# USB_Protect_A.net
KiCad netlist of a schematic drawn in EAGLE
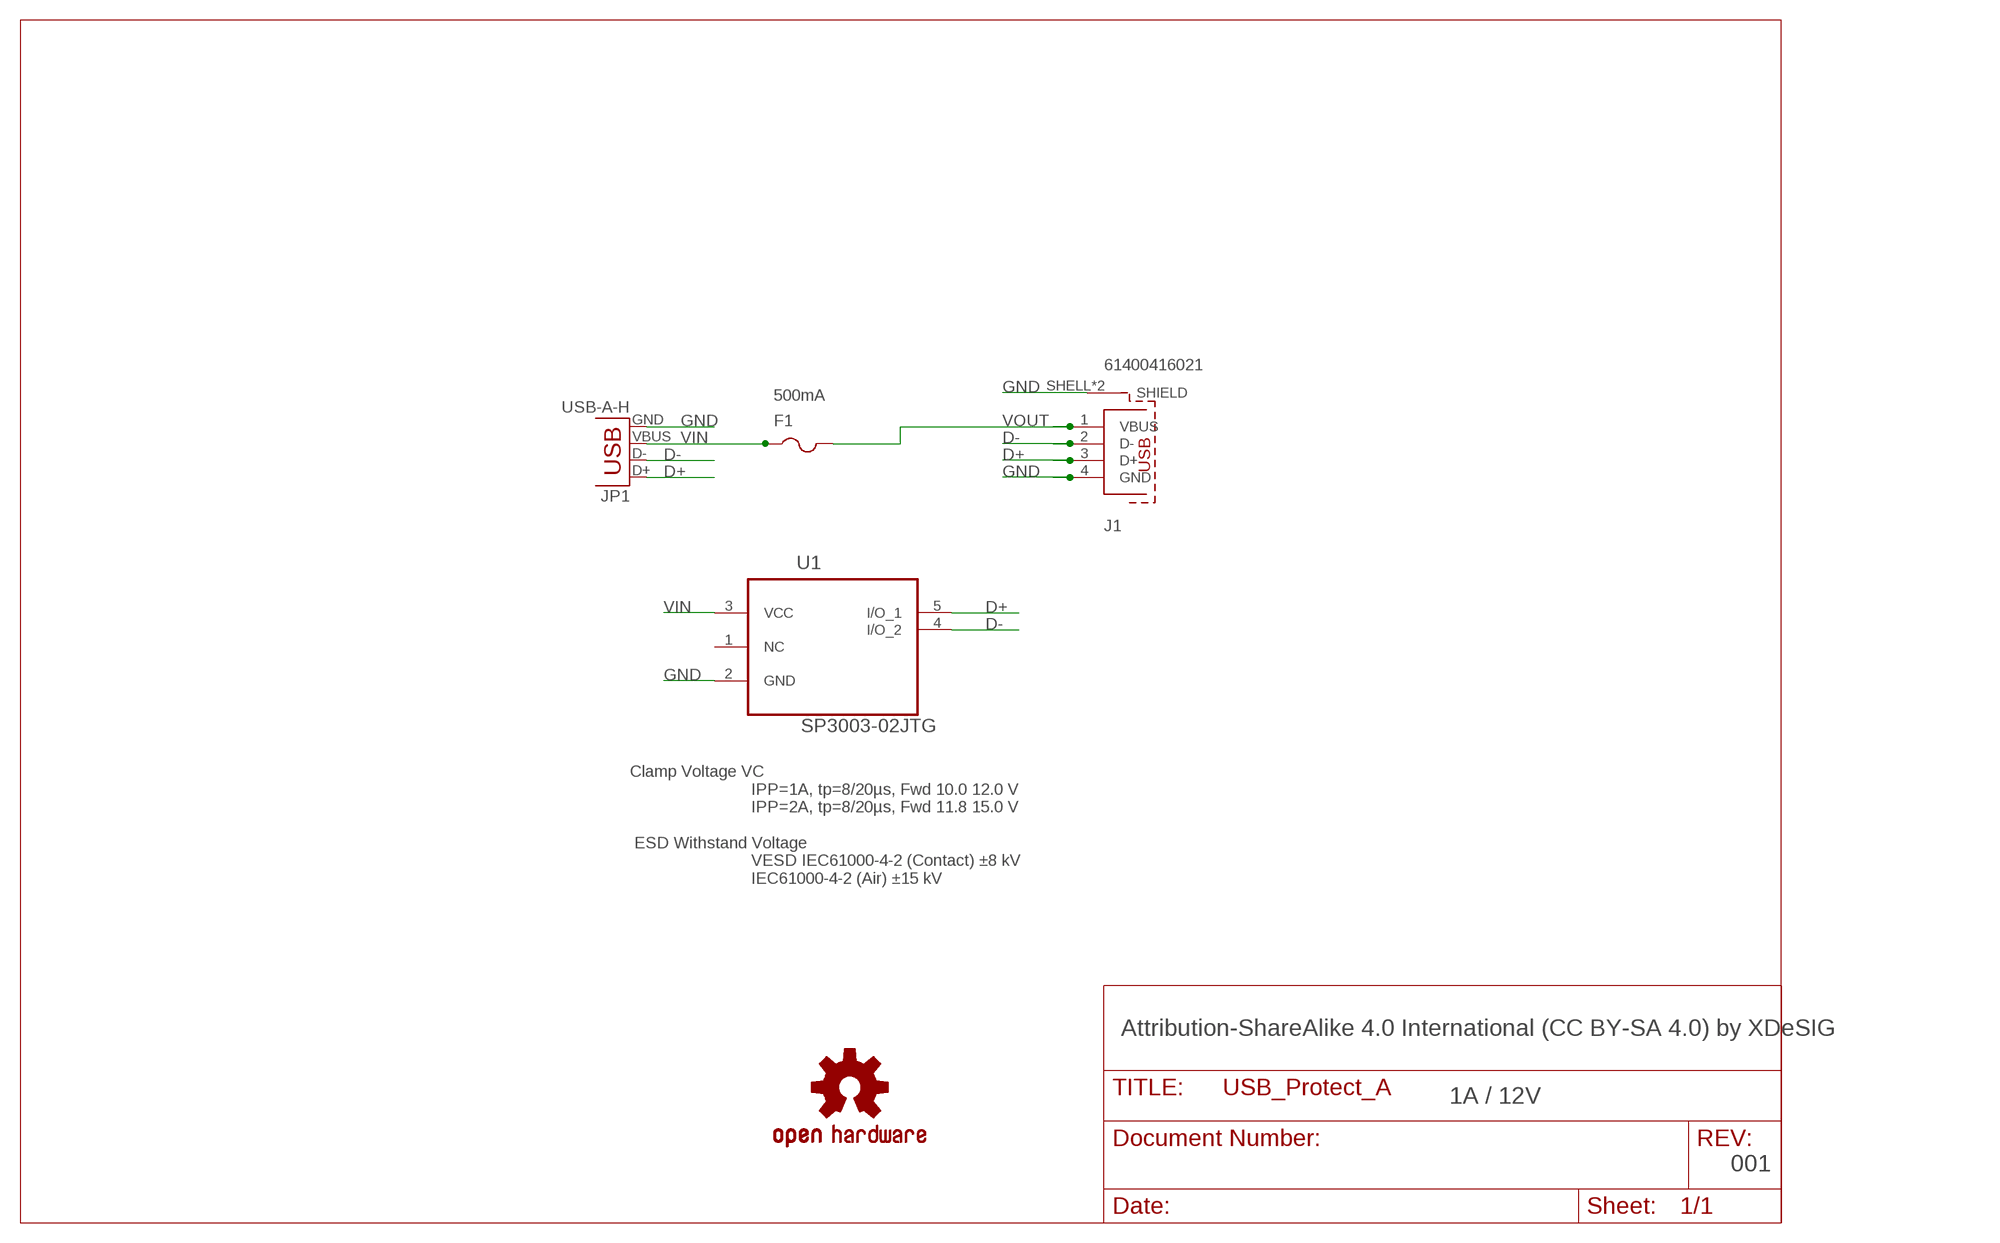
[diagram p0: schematic, sheet 1]

(export (version "E")
  (design (tool "Eeschema 10.0.6"))
  (components
    (comp (ref "F1")
      (value "500mA")
      (footprint "eagle-import:R1206")
      (libsource (lib "eagle-import") (part "PTCFUSE-1206"))
    )
    (comp (ref "J1")
      (value "61400416021")
      (footprint "eagle-import:61400416021")
      (fields (field (name "MF") "Wurth Electronics"))
      (libsource (lib "eagle-import") (part "61400416021"))
    )
    (comp (ref "JP1")
      (value "USB-A-H")
      (footprint "eagle-import:USB-A-H")
      (libsource (lib "eagle-import") (part "USB-A-H"))
    )
    (comp (ref "LOGO1")
      (value "OSHW-LOGOS")
      (footprint "eagle-import:ESCORNA_LBRESCORNA_CPU_2_10_SPARKFUN-AESTHETICS_OSHW-LOGO-S")
      (libsource (lib "eagle-import") (part "OSHW-LOGOS"))
    )
    (comp (ref "U1")
      (value "SP3003-02JTG")
      (footprint "eagle-import:SOT65P220X110-5N")
      (fields (field (name "MF") "Littelfuse"))
      (libsource (lib "eagle-import") (part "SP3003-02JTG"))
    )
  )
  (nets
    (net (code "1") (name "/D+") (class "Default")
      (node (ref "J1") (pin "3") (pinfunction "D+_3") (pintype "bidirectional"))
      (node (ref "JP1") (pin "D+") (pinfunction "D+_D+") (pintype "bidirectional"))
      (node (ref "U1") (pin "5") (pinfunction "I/O_1_5") (pintype "bidirectional"))
    )
    (net (code "2") (name "/D-") (class "Default")
      (node (ref "J1") (pin "2") (pinfunction "D-_2") (pintype "bidirectional"))
      (node (ref "JP1") (pin "D-") (pinfunction "D-_D-") (pintype "bidirectional"))
      (node (ref "U1") (pin "4") (pinfunction "I/O_2_4") (pintype "bidirectional"))
    )
    (net (code "3") (name "/GND") (class "Default")
      (node (ref "J1") (pin "4") (pinfunction "GND_4") (pintype "bidirectional"))
      (node (ref "J1") (pin "SHELL") (pinfunction "SHIELD_SHELL") (pintype "bidirectional"))
      (node (ref "J1") (pin "SHELL1") (pinfunction "SHIELD_SHELL1") (pintype "bidirectional"))
      (node (ref "JP1") (pin "GND") (pinfunction "GND_GND") (pintype "bidirectional"))
      (node (ref "U1") (pin "2") (pinfunction "GND_2") (pintype "passive"))
    )
    (net (code "4") (name "/VIN") (class "Default")
      (node (ref "F1") (pin "1") (pinfunction "1_1") (pintype "passive"))
      (node (ref "JP1") (pin "VBUS") (pinfunction "VBUS_VBUS") (pintype "bidirectional"))
      (node (ref "U1") (pin "3") (pinfunction "VCC_3") (pintype "power_in"))
    )
    (net (code "5") (name "/VOUT") (class "Default")
      (node (ref "F1") (pin "2") (pinfunction "2_2") (pintype "passive"))
      (node (ref "J1") (pin "1") (pinfunction "VBUS_1") (pintype "bidirectional"))
    )
    (net (code "6") (name "unconnected-(U1-NC-Pad1)") (class "Default")
      (node (ref "U1") (pin "1") (pinfunction "NC_1") (pintype "no_connect"))
    )
  )
)
